# FOC_STM32G431.net
KiCad netlist of a schematic drawn in Altium Designer
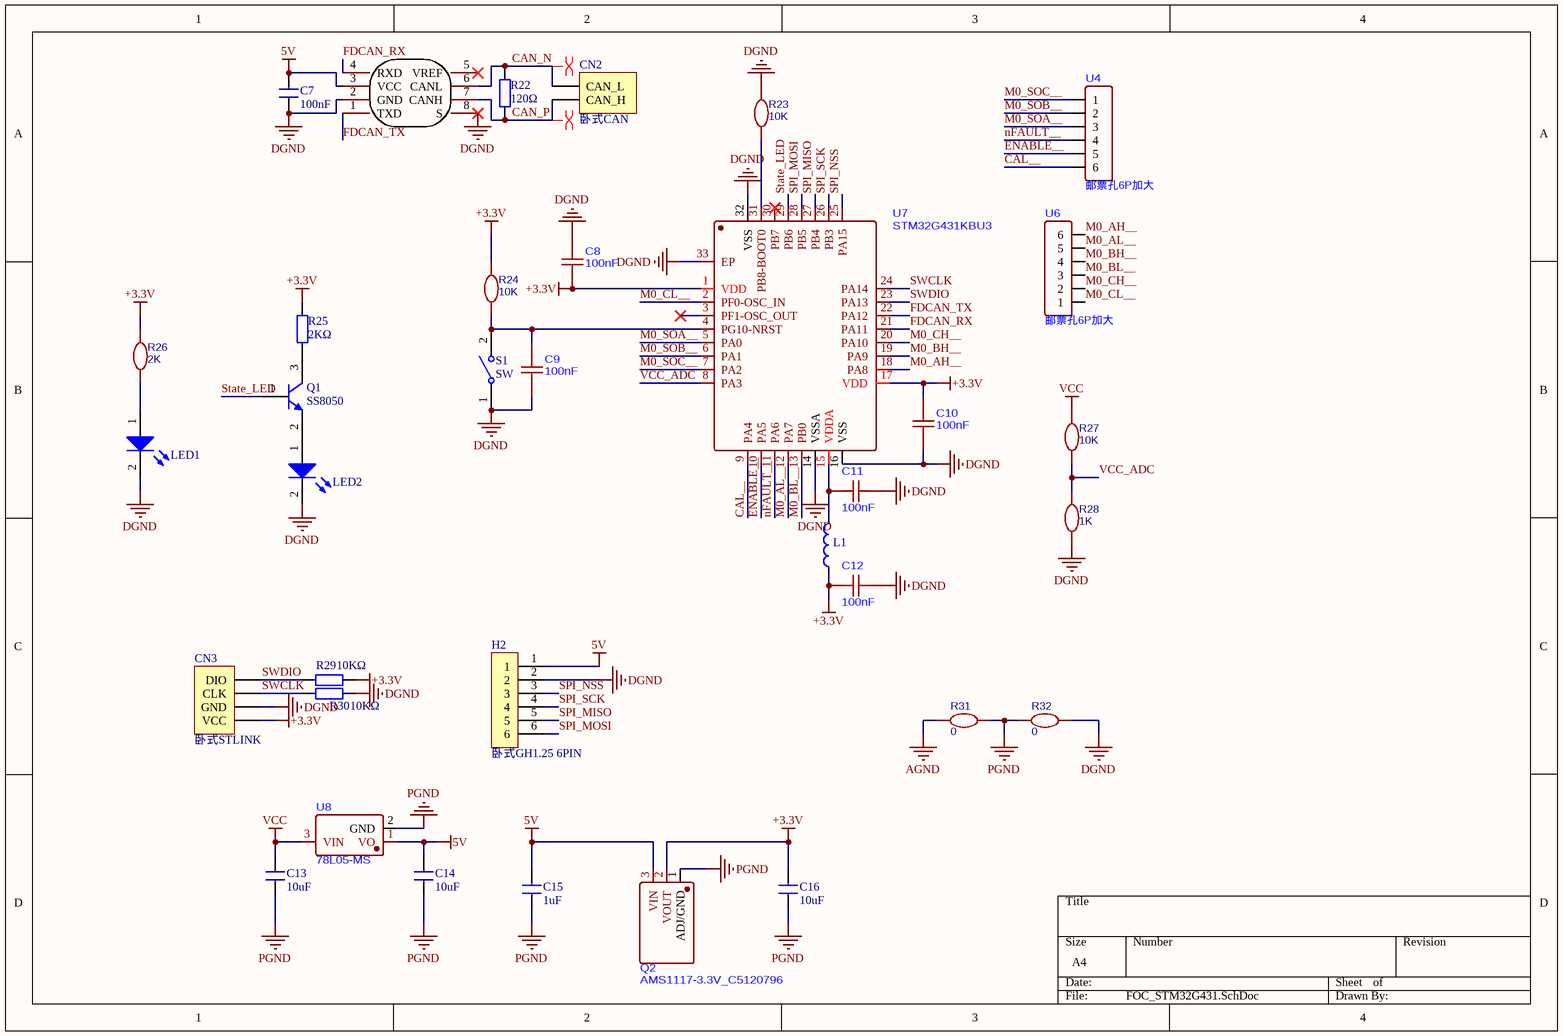
[diagram p0: FOC_STM32G431.SchDoc]

(export (version "E")
  (design (tool "Eeschema 10.0.6"))
  (components
    (comp (ref "C7")
      (value "100nF")
      (footprint "c0402")
      (description "贴片电容0402")
      (libsource (lib "Integrated_Library1") (part "0402贴片电容"))
    )
    (comp (ref "C8") (value "100nF") (footprint "c0402") (libsource (lib "PETO") (part "CC0201JRX7R9BB101")))
    (comp (ref "C9") (value "100nF") (footprint "c0402") (libsource (lib "PETO") (part "CC0201JRX7R9BB101")))
    (comp (ref "C10") (value "100nF") (footprint "c0402") (libsource (lib "PETO") (part "CC0201JRX7R9BB101")))
    (comp (ref "C11") (value "100nF") (footprint "c0402") (libsource (lib "PETO") (part "CC0201JRX7R9BB101")))
    (comp (ref "C12") (value "100nF") (footprint "c0402") (libsource (lib "PETO") (part "CC0201JRX7R9BB101")))
    (comp (ref "C13")
      (value "10uF")
      (footprint "1210")
      (description "1210贴片电容")
      (libsource (lib "Integrated_Library1") (part "1210贴片电容"))
    )
    (comp (ref "C14")
      (value "10uF")
      (footprint "1210")
      (description "1210贴片电容")
      (libsource (lib "Integrated_Library1") (part "1210贴片电容"))
    )
    (comp (ref "C15")
      (value "1uF")
      (footprint "c0402")
      (description "贴片电容0402")
      (libsource (lib "Integrated_Library1") (part "0402贴片电容"))
    )
    (comp (ref "C16")
      (value "10uF")
      (footprint "1210")
      (description "1210贴片电容")
      (libsource (lib "Integrated_Library1") (part "1210贴片电容"))
    )
    (comp (ref "CN2")
      (value "卧式CAN")
      (footprint "GH1.25 2P 卧式")
      (fields (field (name "PUBLISHER") "Altium Limited"))
      (libsource (lib "Integrated_Library1") (part "卧式CAN"))
    )
    (comp (ref "CN3")
      (value "卧式STLINK")
      (footprint "CONN-SMD_4P-P1.25_GH1.25-4P")
      (libsource (lib "Integrated_Library1") (part "卧式STLINK"))
    )
    (comp (ref "H2")
      (value "卧式GH1.25 6PIN")
      (footprint "CONN-SMD_6P-P1.25_XYECONN_XY-GH1.25-6A61")
      (libsource (lib "En") (part "卧式GH1.25 6PIN"))
    )
    (comp (ref "L1")
      (value "1008屏蔽电感")
      (footprint "R0603")
      (libsource (lib "Integrated_Library1") (part "1008屏蔽电感"))
    )
    (comp (ref "LED1")
      (value "LED")
      (footprint "led0805")
      (description "0805贴片LED")
      (libsource (lib "Integrated_Library1") (part "0805贴片LED"))
    )
    (comp (ref "LED2")
      (value "LED")
      (footprint "led0805")
      (description "0805贴片LED")
      (libsource (lib "Integrated_Library1") (part "0805贴片LED"))
    )
    (comp (ref "Q1")
      (value "SS8050")
      (footprint "SOT-23-3_L2.9-W1.3-P1.90-LS2.4-BR")
      (description "三极管")
      (libsource (lib "Integrated_Library1") (part "2N2222"))
    )
    (comp (ref "Q2")
      (value "AMS1117-3.3V_C5120796")
      (footprint "SOT-89-3_L4.5-W2.5-P1.50-LS4.2-BR")
      (libsource (lib "FOC_DRV8323") (part "AMS1117-3.3V_C5120796"))
    )
    (comp (ref "R22")
      (value "120Ω")
      (footprint "R0402")
      (description "0402贴片电阻")
      (libsource (lib "Integrated_Library1") (part "0402贴片电阻"))
    )
    (comp (ref "R23")
      (value "10K")
      (footprint "R0402")
      (fields
        (field (name "BOM_MANUFACTURER PART") "0603WAJ022JT5E")
        (field (name "BOM_SUPPLIER PART") "C25226")
      )
      (libsource (lib "altium-import") (part "root_3_2.2R_"))
    )
    (comp (ref "R24")
      (value "10K")
      (footprint "R0402")
      (fields
        (field (name "BOM_MANUFACTURER PART") "0603WAJ022JT5E")
        (field (name "BOM_SUPPLIER PART") "C25226")
      )
      (libsource (lib "altium-import") (part "root_3_2.2R_"))
    )
    (comp (ref "R25")
      (value "2KΩ")
      (footprint "R0402")
      (description "0402贴片电阻")
      (libsource (lib "Integrated_Library1") (part "0402贴片电阻"))
    )
    (comp (ref "R26")
      (value "2K")
      (footprint "R0402")
      (fields
        (field (name "BOM_MANUFACTURER PART") "0603WAJ022JT5E")
        (field (name "BOM_SUPPLIER PART") "C25226")
      )
      (libsource (lib "altium-import") (part "root_3_2.2R_"))
    )
    (comp (ref "R27")
      (value "10K")
      (footprint "R0402")
      (fields
        (field (name "BOM_MANUFACTURER PART") "0603WAJ022JT5E")
        (field (name "BOM_SUPPLIER PART") "C25226")
      )
      (libsource (lib "altium-import") (part "root_1_2.2R_"))
    )
    (comp (ref "R28")
      (value "1K")
      (footprint "R0402")
      (fields
        (field (name "BOM_MANUFACTURER PART") "0603WAJ022JT5E")
        (field (name "BOM_SUPPLIER PART") "C25226")
      )
      (libsource (lib "altium-import") (part "root_1_2.2R_"))
    )
    (comp (ref "R29")
      (value "10KΩ")
      (footprint "R0402")
      (description "0402贴片电阻")
      (libsource (lib "") (part "0402贴片电阻_1"))
    )
    (comp (ref "R30")
      (value "10KΩ")
      (footprint "R0402")
      (description "0402贴片电阻")
      (libsource (lib "") (part "0402贴片电阻_2"))
    )
    (comp (ref "R31")
      (value "0")
      (footprint "R0402")
      (fields
        (field (name "BOM_MANUFACTURER PART") "0603WAJ022JT5E")
        (field (name "BOM_SUPPLIER PART") "C25226")
      )
      (libsource (lib "altium-import") (part "root_0_2.2R_"))
    )
    (comp (ref "R32")
      (value "0")
      (footprint "R0402")
      (fields
        (field (name "BOM_MANUFACTURER PART") "0603WAJ022JT5E")
        (field (name "BOM_SUPPLIER PART") "C25226")
      )
      (libsource (lib "altium-import") (part "root_0_2.2R_"))
    )
    (comp (ref "S1")
      (value "SW")
      (footprint "KEY_SMD")
      (description "开关")
      (libsource (lib "Integrated_Library1") (part "SW"))
    )
    (comp (ref "U4")
      (value "邮票孔6P加大")
      (footprint "PCBComponent_1 - duplicate")
      (libsource (lib "FOC_DRV8323") (part "邮票孔6P加大"))
    )
    (comp (ref "U5")
      (value "SN65HVD1050DR")
      (footprint "SOIC-8_L4.9-W3.9-P1.27-LS6.0-BL")
      (description "CAN芯片")
      (fields (field (name "MANUFACTURER") "TI(德州仪器)"))
      (libsource (lib "Integrated_Library1") (part "SN65HVD1050DR"))
    )
    (comp (ref "U6")
      (value "邮票孔6P加大")
      (footprint "PCBComponent_1 - duplicate")
      (libsource (lib "FOC_DRV8323") (part "邮票孔6P加大"))
    )
    (comp (ref "U7")
      (value "STM32G431KBU3")
      (footprint "UFQFPN-32_L5.0-W5.0-P0.50-BL-EP3.5")
      (libsource (lib "FOC_DRV8323") (part "STM32G431KBU3"))
    )
    (comp (ref "U8")
      (value "78L05-MS")
      (footprint "SOT-89-3_L4.5-W2.5-P1.50-LS4.2-BR")
      (libsource (lib "FOC_DRV8323") (part "78L05-MS"))
    )
  )
  (nets
    (net (code "1") (name "+3.3V") (class "Default")
      (node (ref "C10") (pin "2") (pinfunction "2_2") (pintype "passive"))
      (node (ref "C12") (pin "2") (pinfunction "2_2") (pintype "passive"))
      (node (ref "C16") (pin "2") (pinfunction "2_2") (pintype "passive"))
      (node (ref "C8") (pin "2") (pinfunction "2_2") (pintype "passive"))
      (node (ref "CN3") (pin "1") (pinfunction "VCC_1") (pintype "passive"))
      (node (ref "L1") (pin "1") (pinfunction "1_1") (pintype "passive"))
      (node (ref "Q2") (pin "2") (pinfunction "VOUT_2") (pintype "passive"))
      (node (ref "R24") (pin "1") (pinfunction "1_1") (pintype "passive"))
      (node (ref "R25") (pin "2") (pinfunction "2_2") (pintype "passive"))
      (node (ref "R26") (pin "1") (pinfunction "1_1") (pintype "passive"))
      (node (ref "R29") (pin "1") (pinfunction "1_1") (pintype "passive"))
      (node (ref "U7") (pin "1") (pinfunction "VDD_1") (pintype "passive"))
      (node (ref "U7") (pin "17") (pinfunction "VDD_17") (pintype "passive"))
    )
    (net (code "2") (name "/CAL__") (class "Default")
      (node (ref "U4") (pin "1") (pinfunction "6_1") (pintype "passive"))
      (node (ref "U7") (pin "9") (pinfunction "PA4_9") (pintype "passive"))
    )
    (net (code "3") (name "/CAN_N") (class "Default")
      (node (ref "CN2") (pin "2") (pinfunction "CAN_L_2") (pintype "passive"))
      (node (ref "R22") (pin "2") (pinfunction "2_2") (pintype "passive"))
      (node (ref "U5") (pin "6") (pinfunction "CANL_6") (pintype "passive"))
    )
    (net (code "4") (name "/CAN_P") (class "Default")
      (node (ref "CN2") (pin "1") (pinfunction "CAN_H_1") (pintype "passive"))
      (node (ref "R22") (pin "1") (pinfunction "1_1") (pintype "passive"))
      (node (ref "U5") (pin "7") (pinfunction "CANH_7") (pintype "passive"))
    )
    (net (code "5") (name "/ENABLE__") (class "Default")
      (node (ref "U4") (pin "2") (pinfunction "5_2") (pintype "passive"))
      (node (ref "U7") (pin "10") (pinfunction "PA5_10") (pintype "passive"))
    )
    (net (code "6") (name "/FDCAN_RX") (class "Default")
      (node (ref "U5") (pin "4") (pinfunction "RXD_4") (pintype "passive"))
      (node (ref "U7") (pin "21") (pinfunction "PA11_21") (pintype "passive"))
    )
    (net (code "7") (name "/FDCAN_TX") (class "Default")
      (node (ref "U5") (pin "1") (pinfunction "TXD_1") (pintype "passive"))
      (node (ref "U7") (pin "22") (pinfunction "PA12_22") (pintype "passive"))
    )
    (net (code "8") (name "/M0_AH__") (class "Default")
      (node (ref "U6") (pin "1") (pinfunction "6_1") (pintype "passive"))
      (node (ref "U7") (pin "18") (pinfunction "PA8_18") (pintype "passive"))
    )
    (net (code "9") (name "/M0_AL__") (class "Default")
      (node (ref "U6") (pin "2") (pinfunction "5_2") (pintype "passive"))
      (node (ref "U7") (pin "12") (pinfunction "PA7_12") (pintype "passive"))
    )
    (net (code "10") (name "/M0_BH__") (class "Default")
      (node (ref "U6") (pin "3") (pinfunction "4_3") (pintype "passive"))
      (node (ref "U7") (pin "19") (pinfunction "PA9_19") (pintype "passive"))
    )
    (net (code "11") (name "/M0_BL__") (class "Default")
      (node (ref "U6") (pin "4") (pinfunction "3_4") (pintype "passive"))
      (node (ref "U7") (pin "13") (pinfunction "PB0_13") (pintype "passive"))
    )
    (net (code "12") (name "/M0_CH__") (class "Default")
      (node (ref "U6") (pin "5") (pinfunction "2_5") (pintype "passive"))
      (node (ref "U7") (pin "20") (pinfunction "PA10_20") (pintype "passive"))
    )
    (net (code "13") (name "/M0_CL__") (class "Default")
      (node (ref "U6") (pin "6") (pinfunction "1_6") (pintype "passive"))
      (node (ref "U7") (pin "2") (pinfunction "PF0-OSC_IN_2") (pintype "passive"))
    )
    (net (code "14") (name "/M0_SOA__") (class "Default")
      (node (ref "U4") (pin "4") (pinfunction "3_4") (pintype "passive"))
      (node (ref "U7") (pin "5") (pinfunction "PA0_5") (pintype "passive"))
    )
    (net (code "15") (name "/M0_SOB__") (class "Default")
      (node (ref "U4") (pin "5") (pinfunction "2_5") (pintype "passive"))
      (node (ref "U7") (pin "6") (pinfunction "PA1_6") (pintype "passive"))
    )
    (net (code "16") (name "/M0_SOC__") (class "Default")
      (node (ref "U4") (pin "6") (pinfunction "1_6") (pintype "passive"))
      (node (ref "U7") (pin "7") (pinfunction "PA2_7") (pintype "passive"))
    )
    (net (code "17") (name "/SPI_MISO") (class "Default")
      (node (ref "H2") (pin "5") (pinfunction "5_5") (pintype "passive"))
      (node (ref "U7") (pin "27") (pinfunction "PB4_27") (pintype "passive"))
    )
    (net (code "18") (name "/SPI_MOSI") (class "Default")
      (node (ref "H2") (pin "6") (pinfunction "6_6") (pintype "passive"))
      (node (ref "U7") (pin "28") (pinfunction "PB5_28") (pintype "passive"))
    )
    (net (code "19") (name "/SPI_NSS") (class "Default")
      (node (ref "H2") (pin "3") (pinfunction "3_3") (pintype "passive"))
      (node (ref "U7") (pin "25") (pinfunction "PA15_25") (pintype "passive"))
    )
    (net (code "20") (name "/SPI_SCK") (class "Default")
      (node (ref "H2") (pin "4") (pinfunction "4_4") (pintype "passive"))
      (node (ref "U7") (pin "26") (pinfunction "PB3_26") (pintype "passive"))
    )
    (net (code "21") (name "/SWCLK") (class "Default")
      (node (ref "CN3") (pin "3") (pinfunction "CLK_3") (pintype "passive"))
      (node (ref "R30") (pin "1") (pinfunction "1_1") (pintype "passive"))
      (node (ref "U7") (pin "24") (pinfunction "PA14_24") (pintype "passive"))
    )
    (net (code "22") (name "/SWDIO") (class "Default")
      (node (ref "CN3") (pin "4") (pinfunction "DIO_4") (pintype "passive"))
      (node (ref "R29") (pin "2") (pinfunction "2_2") (pintype "passive"))
      (node (ref "U7") (pin "23") (pinfunction "PA13_23") (pintype "passive"))
    )
    (net (code "23") (name "/State_LED") (class "Default")
      (node (ref "Q1") (pin "1") (pinfunction "B_1") (pintype "passive"))
      (node (ref "U7") (pin "29") (pinfunction "PB6_29") (pintype "passive"))
    )
    (net (code "24") (name "/VCC_ADC") (class "Default")
      (node (ref "R27") (pin "1") (pinfunction "1_1") (pintype "passive"))
      (node (ref "R28") (pin "2") (pinfunction "2_2") (pintype "passive"))
      (node (ref "U7") (pin "8") (pinfunction "PA3_8") (pintype "passive"))
    )
    (net (code "25") (name "/nFAULT__") (class "Default")
      (node (ref "U4") (pin "3") (pinfunction "4_3") (pintype "passive"))
      (node (ref "U7") (pin "11") (pinfunction "PA6_11") (pintype "passive"))
    )
    (net (code "26") (name "5V") (class "Default")
      (node (ref "C14") (pin "2") (pinfunction "2_2") (pintype "passive"))
      (node (ref "C15") (pin "2") (pinfunction "2_2") (pintype "passive"))
      (node (ref "C7") (pin "2") (pinfunction "2_2") (pintype "passive"))
      (node (ref "H2") (pin "1") (pinfunction "1_1") (pintype "passive"))
      (node (ref "Q2") (pin "3") (pinfunction "VIN_3") (pintype "passive"))
      (node (ref "U5") (pin "3") (pinfunction "VCC_3") (pintype "passive"))
      (node (ref "U8") (pin "1") (pinfunction "VO_1") (pintype "passive"))
    )
    (net (code "27") (name "AGND") (class "Default")
      (node (ref "R31") (pin "1") (pinfunction "1_1") (pintype "passive"))
    )
    (net (code "28") (name "DGND") (class "Default")
      (node (ref "C10") (pin "1") (pinfunction "1_1") (pintype "passive"))
      (node (ref "C11") (pin "1") (pinfunction "1_1") (pintype "passive"))
      (node (ref "C12") (pin "1") (pinfunction "1_1") (pintype "passive"))
      (node (ref "C7") (pin "1") (pinfunction "1_1") (pintype "passive"))
      (node (ref "C8") (pin "1") (pinfunction "1_1") (pintype "passive"))
      (node (ref "C9") (pin "1") (pinfunction "1_1") (pintype "passive"))
      (node (ref "CN3") (pin "2") (pinfunction "GND_2") (pintype "passive"))
      (node (ref "H2") (pin "2") (pinfunction "2_2") (pintype "passive"))
      (node (ref "LED1") (pin "2") (pinfunction "K_2") (pintype "passive"))
      (node (ref "LED2") (pin "2") (pinfunction "K_2") (pintype "passive"))
      (node (ref "R23") (pin "1") (pinfunction "1_1") (pintype "passive"))
      (node (ref "R28") (pin "1") (pinfunction "1_1") (pintype "passive"))
      (node (ref "R30") (pin "2") (pinfunction "2_2") (pintype "passive"))
      (node (ref "R32") (pin "2") (pinfunction "2_2") (pintype "passive"))
      (node (ref "S1") (pin "1") (pinfunction "COMMON_1") (pintype "passive"))
      (node (ref "U5") (pin "2") (pinfunction "GND_2") (pintype "passive"))
      (node (ref "U5") (pin "8") (pinfunction "S_8") (pintype "passive"))
      (node (ref "U7") (pin "14") (pinfunction "VSSA_14") (pintype "passive"))
      (node (ref "U7") (pin "16") (pinfunction "VSS_16") (pintype "passive"))
      (node (ref "U7") (pin "32") (pinfunction "VSS_32") (pintype "passive"))
      (node (ref "U7") (pin "33") (pinfunction "EP_33") (pintype "passive"))
    )
    (net (code "29") (name "Net-(LED1-A)") (class "Default")
      (node (ref "LED1") (pin "1") (pinfunction "A_1") (pintype "passive"))
      (node (ref "R26") (pin "2") (pinfunction "2_2") (pintype "passive"))
    )
    (net (code "30") (name "Net-(LED2-A)") (class "Default")
      (node (ref "LED2") (pin "1") (pinfunction "A_1") (pintype "passive"))
      (node (ref "Q1") (pin "2") (pinfunction "E_2") (pintype "passive"))
    )
    (net (code "31") (name "Net-(Q1-C)") (class "Default")
      (node (ref "Q1") (pin "3") (pinfunction "C_3") (pintype "passive"))
      (node (ref "R25") (pin "1") (pinfunction "1_1") (pintype "passive"))
    )
    (net (code "32") (name "Net-(S1-NO)") (class "Default")
      (node (ref "C9") (pin "2") (pinfunction "2_2") (pintype "passive"))
      (node (ref "R24") (pin "2") (pinfunction "2_2") (pintype "passive"))
      (node (ref "S1") (pin "2") (pinfunction "NO_2") (pintype "passive"))
      (node (ref "U7") (pin "4") (pinfunction "PG10-NRST_4") (pintype "passive"))
    )
    (net (code "33") (name "Net-(U7-PB8-BOOT0)") (class "Default")
      (node (ref "R23") (pin "2") (pinfunction "2_2") (pintype "passive"))
      (node (ref "U7") (pin "31") (pinfunction "PB8-BOOT0_31") (pintype "passive"))
    )
    (net (code "34") (name "Net-(U7-VDDA)") (class "Default")
      (node (ref "C11") (pin "2") (pinfunction "2_2") (pintype "passive"))
      (node (ref "L1") (pin "2") (pinfunction "2_2") (pintype "passive"))
      (node (ref "U7") (pin "15") (pinfunction "VDDA_15") (pintype "passive"))
    )
    (net (code "35") (name "PGND") (class "Default")
      (node (ref "C13") (pin "1") (pinfunction "1_1") (pintype "passive"))
      (node (ref "C14") (pin "1") (pinfunction "1_1") (pintype "passive"))
      (node (ref "C15") (pin "1") (pinfunction "1_1") (pintype "passive"))
      (node (ref "C16") (pin "1") (pinfunction "1_1") (pintype "passive"))
      (node (ref "Q2") (pin "1") (pinfunction "ADJ/GND_1") (pintype "passive"))
      (node (ref "R31") (pin "2") (pinfunction "2_2") (pintype "passive"))
      (node (ref "R32") (pin "1") (pinfunction "1_1") (pintype "passive"))
      (node (ref "U8") (pin "2") (pinfunction "GND_2") (pintype "passive"))
    )
    (net (code "36") (name "VCC") (class "Default")
      (node (ref "C13") (pin "2") (pinfunction "2_2") (pintype "passive"))
      (node (ref "R27") (pin "2") (pinfunction "2_2") (pintype "passive"))
      (node (ref "U8") (pin "3") (pinfunction "VIN_3") (pintype "passive"))
    )
    (net (code "37") (name "unconnected-(U5-VREF-Pad5)") (class "Default")
      (node (ref "U5") (pin "5") (pinfunction "VREF_5") (pintype "passive+no_connect"))
    )
    (net (code "38") (name "unconnected-(U7-PB7-Pad30)") (class "Default")
      (node (ref "U7") (pin "30") (pinfunction "PB7_30") (pintype "passive+no_connect"))
    )
    (net (code "39") (name "unconnected-(U7-PF1-OSC_OUT-Pad3)") (class "Default")
      (node (ref "U7") (pin "3") (pinfunction "PF1-OSC_OUT_3") (pintype "passive+no_connect"))
    )
  )
)
